# M139A.net
KiCad netlist of a schematic drawn in EAGLE
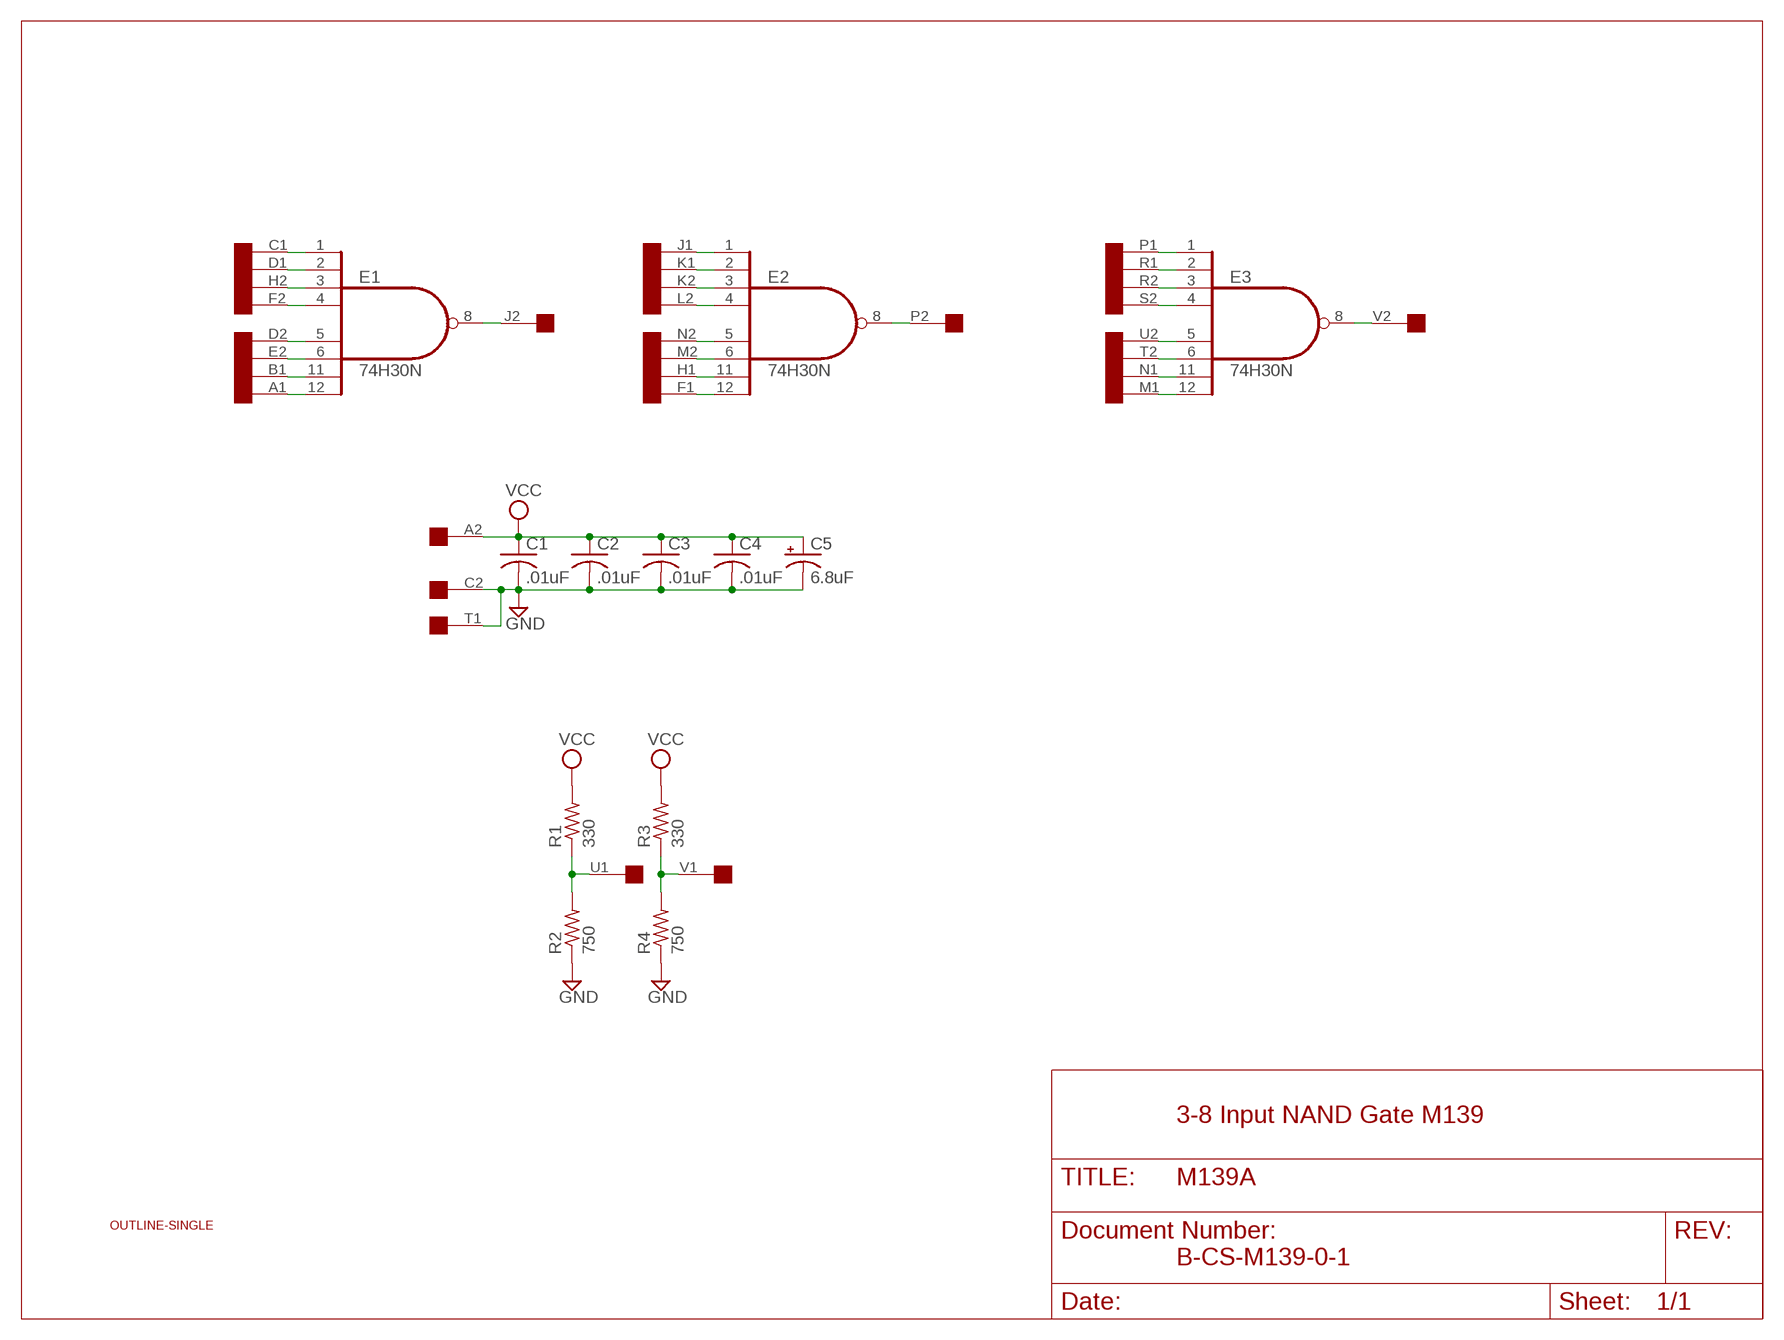
[diagram p0: schematic, sheet 1]

(export (version "E")
  (design (tool "Eeschema 10.0.6"))
  (components
    (comp (ref "C1")
      (value ".01uF")
      (footprint "eagle-import:C050-025X075")
      (libsource (lib "eagle-import") (part "C-US050-025X075"))
    )
    (comp (ref "C2")
      (value ".01uF")
      (footprint "eagle-import:C050-025X075")
      (libsource (lib "eagle-import") (part "C-US050-025X075"))
    )
    (comp (ref "C3")
      (value ".01uF")
      (footprint "eagle-import:C050-025X075")
      (libsource (lib "eagle-import") (part "C-US050-025X075"))
    )
    (comp (ref "C4")
      (value ".01uF")
      (footprint "eagle-import:C050-025X075")
      (libsource (lib "eagle-import") (part "C-US050-025X075"))
    )
    (comp (ref "C5")
      (value "6.8uF")
      (footprint "eagle-import:E12-8")
      (libsource (lib "eagle-import") (part "CPOL-USE20-8AXIAL"))
    )
    (comp (ref "E1")
      (value "74H30N")
      (footprint "eagle-import:DIL14")
      (libsource (lib "eagle-import") (part "7430NS"))
    )
    (comp (ref "E2")
      (value "74H30N")
      (footprint "eagle-import:DIL14")
      (libsource (lib "eagle-import") (part "7430NS"))
    )
    (comp (ref "E3")
      (value "74H30N")
      (footprint "eagle-import:DIL14")
      (libsource (lib "eagle-import") (part "7430NS"))
    )
    (comp (ref "R1")
      (value "330")
      (footprint "eagle-import:0207_10")
      (libsource (lib "eagle-import") (part "R-US_0207/10"))
    )
    (comp (ref "R2")
      (value "750")
      (footprint "eagle-import:0207_10")
      (libsource (lib "eagle-import") (part "R-US_0207/10"))
    )
    (comp (ref "R3")
      (value "330")
      (footprint "eagle-import:0207_10")
      (libsource (lib "eagle-import") (part "R-US_0207/10"))
    )
    (comp (ref "R4")
      (value "750")
      (footprint "eagle-import:0207_10")
      (libsource (lib "eagle-import") (part "R-US_0207/10"))
    )
    (comp (ref "U$1")
      (value "OUTLINE-SINGLE")
      (footprint "eagle-import:SINGLE")
      (libsource (lib "eagle-import") (part "OUTLINE-SINGLE"))
    )
    (comp (ref "U$2")
      (value "SINGLE")
      (footprint "eagle-import:EDGE-CON2")
      (libsource (lib "eagle-import") (part "SINGLE"))
    )
  )
  (nets
    (net (code "1") (name "GND") (class "Default")
      (node (ref "C1") (pin "2") (pinfunction "2_2") (pintype "passive"))
      (node (ref "C2") (pin "2") (pinfunction "2_2") (pintype "passive"))
      (node (ref "C3") (pin "2") (pinfunction "2_2") (pintype "passive"))
      (node (ref "C4") (pin "2") (pinfunction "2_2") (pintype "passive"))
      (node (ref "C5") (pin "-") (pinfunction "-_-") (pintype "passive"))
      (node (ref "R2") (pin "1") (pinfunction "1_1") (pintype "passive"))
      (node (ref "R4") (pin "1") (pinfunction "1_1") (pintype "passive"))
      (node (ref "U$2") (pin "C2") (pinfunction "1_C2") (pintype "bidirectional"))
      (node (ref "U$2") (pin "T1") (pinfunction "1_T1") (pintype "bidirectional"))
    )
    (net (code "2") (name "Net-(E1D-I0)") (class "Default")
      (node (ref "E1") (pin "1") (pinfunction "I0_1") (pintype "input"))
      (node (ref "U$2") (pin "C1") (pinfunction "1_C1") (pintype "bidirectional"))
    )
    (net (code "3") (name "Net-(E1D-I1)") (class "Default")
      (node (ref "E1") (pin "2") (pinfunction "I1_2") (pintype "input"))
      (node (ref "U$2") (pin "D1") (pinfunction "1_D1") (pintype "bidirectional"))
    )
    (net (code "4") (name "Net-(E1D-I2)") (class "Default")
      (node (ref "E1") (pin "3") (pinfunction "I2_3") (pintype "input"))
      (node (ref "U$2") (pin "H2") (pinfunction "1_H2") (pintype "bidirectional"))
    )
    (net (code "5") (name "Net-(E1D-I3)") (class "Default")
      (node (ref "E1") (pin "4") (pinfunction "I3_4") (pintype "input"))
      (node (ref "U$2") (pin "F2") (pinfunction "1_F2") (pintype "bidirectional"))
    )
    (net (code "6") (name "Net-(E1D-I4)") (class "Default")
      (node (ref "E1") (pin "5") (pinfunction "I4_5") (pintype "input"))
      (node (ref "U$2") (pin "D2") (pinfunction "1_D2") (pintype "bidirectional"))
    )
    (net (code "7") (name "Net-(E1D-I5)") (class "Default")
      (node (ref "E1") (pin "6") (pinfunction "I5_6") (pintype "input"))
      (node (ref "U$2") (pin "E2") (pinfunction "1_E2") (pintype "bidirectional"))
    )
    (net (code "8") (name "Net-(E1D-I6)") (class "Default")
      (node (ref "E1") (pin "11") (pinfunction "I6_11") (pintype "input"))
      (node (ref "U$2") (pin "B1") (pinfunction "1_B1") (pintype "bidirectional"))
    )
    (net (code "9") (name "Net-(E1D-I7)") (class "Default")
      (node (ref "E1") (pin "12") (pinfunction "I7_12") (pintype "input"))
      (node (ref "U$2") (pin "A1") (pinfunction "1_A1") (pintype "bidirectional"))
    )
    (net (code "10") (name "Net-(E1D-O)") (class "Default")
      (node (ref "E1") (pin "8") (pinfunction "O_8") (pintype "output"))
      (node (ref "U$2") (pin "J2") (pinfunction "1_J2") (pintype "bidirectional"))
    )
    (net (code "11") (name "Net-(E2D-I0)") (class "Default")
      (node (ref "E2") (pin "1") (pinfunction "I0_1") (pintype "input"))
      (node (ref "U$2") (pin "J1") (pinfunction "1_J1") (pintype "bidirectional"))
    )
    (net (code "12") (name "Net-(E2D-I1)") (class "Default")
      (node (ref "E2") (pin "2") (pinfunction "I1_2") (pintype "input"))
      (node (ref "U$2") (pin "K1") (pinfunction "1_K1") (pintype "bidirectional"))
    )
    (net (code "13") (name "Net-(E2D-I2)") (class "Default")
      (node (ref "E2") (pin "3") (pinfunction "I2_3") (pintype "input"))
      (node (ref "U$2") (pin "K2") (pinfunction "1_K2") (pintype "bidirectional"))
    )
    (net (code "14") (name "Net-(E2D-I3)") (class "Default")
      (node (ref "E2") (pin "4") (pinfunction "I3_4") (pintype "input"))
      (node (ref "U$2") (pin "L2") (pinfunction "1_L2") (pintype "bidirectional"))
    )
    (net (code "15") (name "Net-(E2D-I4)") (class "Default")
      (node (ref "E2") (pin "5") (pinfunction "I4_5") (pintype "input"))
      (node (ref "U$2") (pin "N2") (pinfunction "1_N2") (pintype "bidirectional"))
    )
    (net (code "16") (name "Net-(E2D-I5)") (class "Default")
      (node (ref "E2") (pin "6") (pinfunction "I5_6") (pintype "input"))
      (node (ref "U$2") (pin "M2") (pinfunction "1_M2") (pintype "bidirectional"))
    )
    (net (code "17") (name "Net-(E2D-I6)") (class "Default")
      (node (ref "E2") (pin "11") (pinfunction "I6_11") (pintype "input"))
      (node (ref "U$2") (pin "H1") (pinfunction "1_H1") (pintype "bidirectional"))
    )
    (net (code "18") (name "Net-(E2D-I7)") (class "Default")
      (node (ref "E2") (pin "12") (pinfunction "I7_12") (pintype "input"))
      (node (ref "U$2") (pin "F1") (pinfunction "1_F1") (pintype "bidirectional"))
    )
    (net (code "19") (name "Net-(E2D-O)") (class "Default")
      (node (ref "E2") (pin "8") (pinfunction "O_8") (pintype "output"))
      (node (ref "U$2") (pin "P2") (pinfunction "1_P2") (pintype "bidirectional"))
    )
    (net (code "20") (name "Net-(E3D-I0)") (class "Default")
      (node (ref "E3") (pin "1") (pinfunction "I0_1") (pintype "input"))
      (node (ref "U$2") (pin "P1") (pinfunction "1_P1") (pintype "bidirectional"))
    )
    (net (code "21") (name "Net-(E3D-I1)") (class "Default")
      (node (ref "E3") (pin "2") (pinfunction "I1_2") (pintype "input"))
      (node (ref "U$2") (pin "R1") (pinfunction "1_R1") (pintype "bidirectional"))
    )
    (net (code "22") (name "Net-(E3D-I2)") (class "Default")
      (node (ref "E3") (pin "3") (pinfunction "I2_3") (pintype "input"))
      (node (ref "U$2") (pin "R2") (pinfunction "1_R2") (pintype "bidirectional"))
    )
    (net (code "23") (name "Net-(E3D-I3)") (class "Default")
      (node (ref "E3") (pin "4") (pinfunction "I3_4") (pintype "input"))
      (node (ref "U$2") (pin "S2") (pinfunction "1_S2") (pintype "bidirectional"))
    )
    (net (code "24") (name "Net-(E3D-I4)") (class "Default")
      (node (ref "E3") (pin "5") (pinfunction "I4_5") (pintype "input"))
      (node (ref "U$2") (pin "U2") (pinfunction "1_U2") (pintype "bidirectional"))
    )
    (net (code "25") (name "Net-(E3D-I5)") (class "Default")
      (node (ref "E3") (pin "6") (pinfunction "I5_6") (pintype "input"))
      (node (ref "U$2") (pin "T2") (pinfunction "1_T2") (pintype "bidirectional"))
    )
    (net (code "26") (name "Net-(E3D-I6)") (class "Default")
      (node (ref "E3") (pin "11") (pinfunction "I6_11") (pintype "input"))
      (node (ref "U$2") (pin "N1") (pinfunction "1_N1") (pintype "bidirectional"))
    )
    (net (code "27") (name "Net-(E3D-I7)") (class "Default")
      (node (ref "E3") (pin "12") (pinfunction "I7_12") (pintype "input"))
      (node (ref "U$2") (pin "M1") (pinfunction "1_M1") (pintype "bidirectional"))
    )
    (net (code "28") (name "Net-(E3D-O)") (class "Default")
      (node (ref "E3") (pin "8") (pinfunction "O_8") (pintype "output"))
      (node (ref "U$2") (pin "V2") (pinfunction "1_V2") (pintype "bidirectional"))
    )
    (net (code "29") (name "Net-(U$2AG-1)") (class "Default")
      (node (ref "R1") (pin "1") (pinfunction "1_1") (pintype "passive"))
      (node (ref "R2") (pin "2") (pinfunction "2_2") (pintype "passive"))
      (node (ref "U$2") (pin "U1") (pinfunction "1_U1") (pintype "bidirectional"))
    )
    (net (code "30") (name "Net-(U$2AI-1)") (class "Default")
      (node (ref "R3") (pin "1") (pinfunction "1_1") (pintype "passive"))
      (node (ref "R4") (pin "2") (pinfunction "2_2") (pintype "passive"))
      (node (ref "U$2") (pin "V1") (pinfunction "1_V1") (pintype "bidirectional"))
    )
    (net (code "31") (name "VCC") (class "Default")
      (node (ref "C1") (pin "1") (pinfunction "1_1") (pintype "passive"))
      (node (ref "C2") (pin "1") (pinfunction "1_1") (pintype "passive"))
      (node (ref "C3") (pin "1") (pinfunction "1_1") (pintype "passive"))
      (node (ref "C4") (pin "1") (pinfunction "1_1") (pintype "passive"))
      (node (ref "C5") (pin "+") (pinfunction "+_+") (pintype "passive"))
      (node (ref "R1") (pin "2") (pinfunction "2_2") (pintype "passive"))
      (node (ref "R3") (pin "2") (pinfunction "2_2") (pintype "passive"))
      (node (ref "U$2") (pin "A2") (pinfunction "1_A2") (pintype "bidirectional"))
    )
  )
)
